# glove-shield.net
KiCad netlist of a schematic drawn in EAGLE
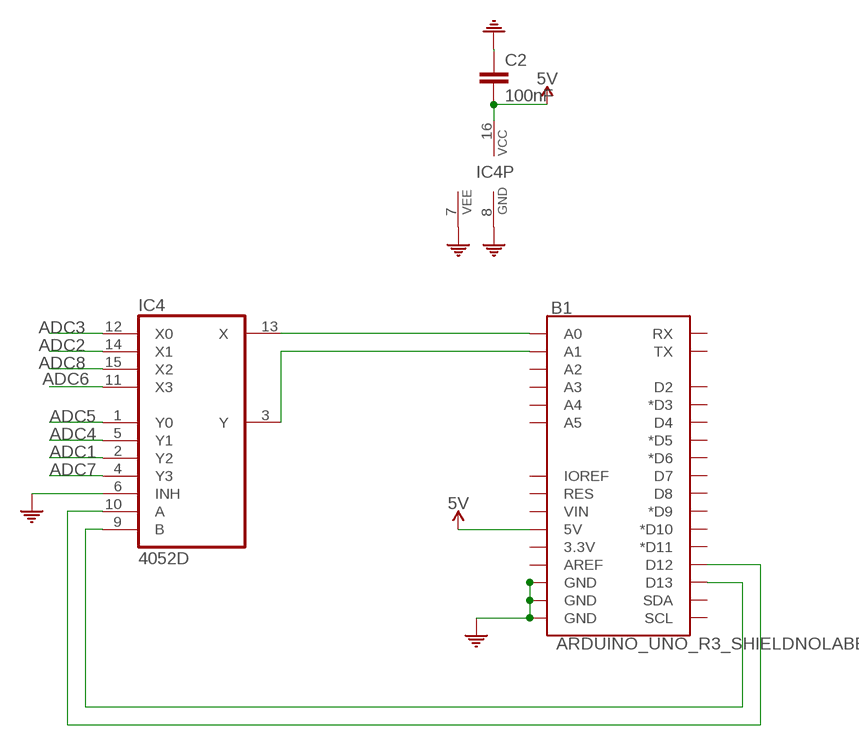
[diagram p0: schematic, sheet 1]
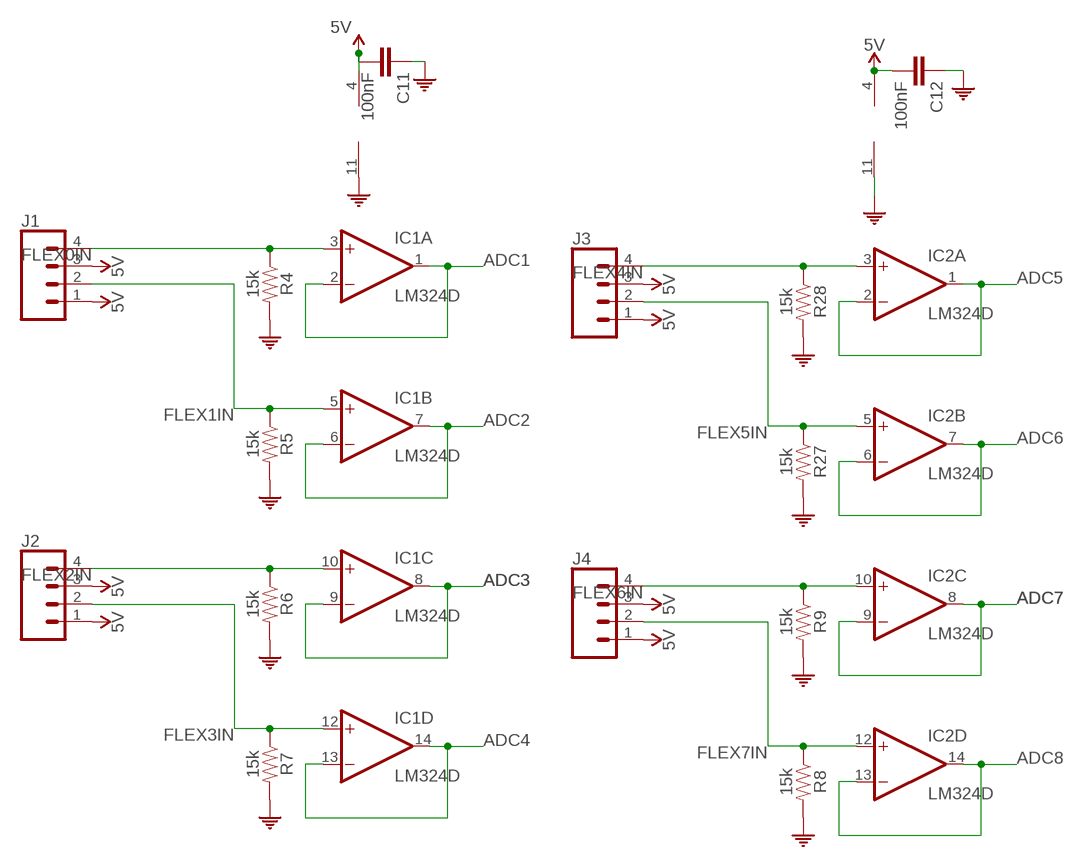
[diagram p1: schematic, sheet 2]

(export (version "E")
  (design (tool "Eeschema 10.0.6"))
  (components
    (comp (ref "C11")
      (value "100nF")
      (footprint "eagle-import:C0603-ROUND")
      (fields (field (name "PART_NUMBER") "cl10b104kbnc"))
      (libsource (lib "eagle-import") (part "0015_100NF_0603"))
    )
    (comp (ref "C12")
      (value "100nF")
      (footprint "eagle-import:C0603-ROUND")
      (fields (field (name "PART_NUMBER") "cl10b104kbnc"))
      (libsource (lib "eagle-import") (part "0015_100NF_0603"))
    )
    (comp (ref "IC1")
      (value "LM324D")
      (footprint "eagle-import:SO14")
      (libsource (lib "eagle-import") (part "LM324D"))
    )
    (comp (ref "IC2")
      (value "LM324D")
      (footprint "eagle-import:SO14")
      (libsource (lib "eagle-import") (part "LM324D"))
    )
    (comp (ref "J1")
      (value "CONN_04JST-PTH")
      (footprint "eagle-import:JST-4-PTH")
      (libsource (lib "eagle-import") (part "CONN_04JST-PTH"))
    )
    (comp (ref "J2")
      (value "CONN_04JST-PTH")
      (footprint "eagle-import:JST-4-PTH")
      (libsource (lib "eagle-import") (part "CONN_04JST-PTH"))
    )
    (comp (ref "J3")
      (value "CONN_04JST-PTH")
      (footprint "eagle-import:JST-4-PTH")
      (libsource (lib "eagle-import") (part "CONN_04JST-PTH"))
    )
    (comp (ref "J4")
      (value "CONN_04JST-PTH")
      (footprint "eagle-import:JST-4-PTH")
      (libsource (lib "eagle-import") (part "CONN_04JST-PTH"))
    )
    (comp (ref "R4")
      (value "15k")
      (footprint "eagle-import:0603")
      (libsource (lib "eagle-import") (part "RESISTOR0603"))
    )
    (comp (ref "R5")
      (value "15k")
      (footprint "eagle-import:0603")
      (libsource (lib "eagle-import") (part "RESISTOR0603"))
    )
    (comp (ref "R6")
      (value "15k")
      (footprint "eagle-import:0603")
      (libsource (lib "eagle-import") (part "RESISTOR0603"))
    )
    (comp (ref "R7")
      (value "15k")
      (footprint "eagle-import:0603")
      (libsource (lib "eagle-import") (part "RESISTOR0603"))
    )
    (comp (ref "R8")
      (value "15k")
      (footprint "eagle-import:0603")
      (libsource (lib "eagle-import") (part "RESISTOR0603"))
    )
    (comp (ref "R9")
      (value "15k")
      (footprint "eagle-import:0603")
      (libsource (lib "eagle-import") (part "RESISTOR0603"))
    )
    (comp (ref "R27")
      (value "15k")
      (footprint "eagle-import:0603")
      (libsource (lib "eagle-import") (part "RESISTOR0603"))
    )
    (comp (ref "R28")
      (value "15k")
      (footprint "eagle-import:0603")
      (libsource (lib "eagle-import") (part "RESISTOR0603"))
    )
    (comp (ref "B1")
      (value "ARDUINO_UNO_R3_SHIELDNOLABELS")
      (footprint "eagle-import:UNO_R3_SHIELD_NOLABELS")
      (libsource (lib "eagle-import") (part "ARDUINO_UNO_R3_SHIELDNOLABELS"))
    )
    (comp (ref "C2")
      (value "100nF")
      (footprint "eagle-import:C0603-ROUND")
      (fields (field (name "PART_NUMBER") "cl10b104kbnc"))
      (libsource (lib "eagle-import") (part "0015_100NF_0603"))
    )
    (comp (ref "IC4")
      (value "4052D")
      (footprint "eagle-import:SO16")
      (libsource (lib "eagle-import") (part "4052D"))
    )
  )
  (nets
    (net (code "1") (name "5V") (class "Default")
      (node (ref "B1") (pin "5V") (pinfunction "5V_5V") (pintype "bidirectional"))
      (node (ref "C11") (pin "2") (pinfunction "2_2") (pintype "passive"))
      (node (ref "C12") (pin "2") (pinfunction "2_2") (pintype "passive"))
      (node (ref "C2") (pin "2") (pinfunction "2_2") (pintype "passive"))
      (node (ref "IC1") (pin "4") (pinfunction "V+_4") (pintype "power_in"))
      (node (ref "IC2") (pin "4") (pinfunction "V+_4") (pintype "power_in"))
      (node (ref "IC4") (pin "16") (pinfunction "VCC_16") (pintype "power_in"))
      (node (ref "J1") (pin "1") (pinfunction "1_1") (pintype "passive"))
      (node (ref "J1") (pin "3") (pinfunction "3_3") (pintype "passive"))
      (node (ref "J2") (pin "1") (pinfunction "1_1") (pintype "passive"))
      (node (ref "J2") (pin "3") (pinfunction "3_3") (pintype "passive"))
      (node (ref "J3") (pin "1") (pinfunction "1_1") (pintype "passive"))
      (node (ref "J3") (pin "3") (pinfunction "3_3") (pintype "passive"))
      (node (ref "J4") (pin "1") (pinfunction "1_1") (pintype "passive"))
      (node (ref "J4") (pin "3") (pinfunction "3_3") (pintype "passive"))
    )
    (net (code "2") (name "ADC1") (class "Default")
      (node (ref "IC1") (pin "1") (pinfunction "OUT_1") (pintype "output"))
      (node (ref "IC1") (pin "2") (pinfunction "-IN_2") (pintype "input"))
      (node (ref "IC4") (pin "2") (pinfunction "Y2_2") (pintype "bidirectional"))
    )
    (net (code "3") (name "ADC2") (class "Default")
      (node (ref "IC1") (pin "6") (pinfunction "-IN_6") (pintype "input"))
      (node (ref "IC1") (pin "7") (pinfunction "OUT_7") (pintype "output"))
      (node (ref "IC4") (pin "14") (pinfunction "X1_14") (pintype "bidirectional"))
    )
    (net (code "4") (name "ADC3") (class "Default")
      (node (ref "IC1") (pin "8") (pinfunction "OUT_8") (pintype "output"))
      (node (ref "IC1") (pin "9") (pinfunction "-IN_9") (pintype "input"))
      (node (ref "IC4") (pin "12") (pinfunction "X0_12") (pintype "bidirectional"))
    )
    (net (code "5") (name "ADC4") (class "Default")
      (node (ref "IC1") (pin "13") (pinfunction "-IN_13") (pintype "input"))
      (node (ref "IC1") (pin "14") (pinfunction "OUT_14") (pintype "output"))
      (node (ref "IC4") (pin "5") (pinfunction "Y1_5") (pintype "bidirectional"))
    )
    (net (code "6") (name "ADC5") (class "Default")
      (node (ref "IC2") (pin "1") (pinfunction "OUT_1") (pintype "output"))
      (node (ref "IC2") (pin "2") (pinfunction "-IN_2") (pintype "input"))
      (node (ref "IC4") (pin "1") (pinfunction "Y0_1") (pintype "bidirectional"))
    )
    (net (code "7") (name "ADC6") (class "Default")
      (node (ref "IC2") (pin "6") (pinfunction "-IN_6") (pintype "input"))
      (node (ref "IC2") (pin "7") (pinfunction "OUT_7") (pintype "output"))
      (node (ref "IC4") (pin "11") (pinfunction "X3_11") (pintype "bidirectional"))
    )
    (net (code "8") (name "ADC7") (class "Default")
      (node (ref "IC2") (pin "8") (pinfunction "OUT_8") (pintype "output"))
      (node (ref "IC2") (pin "9") (pinfunction "-IN_9") (pintype "input"))
      (node (ref "IC4") (pin "4") (pinfunction "Y3_4") (pintype "bidirectional"))
    )
    (net (code "9") (name "ADC8") (class "Default")
      (node (ref "IC2") (pin "13") (pinfunction "-IN_13") (pintype "input"))
      (node (ref "IC2") (pin "14") (pinfunction "OUT_14") (pintype "output"))
      (node (ref "IC4") (pin "15") (pinfunction "X2_15") (pintype "bidirectional"))
    )
    (net (code "10") (name "COM") (class "Default")
      (node (ref "B1") (pin "GND@0") (pinfunction "GND_GND@0") (pintype "bidirectional"))
      (node (ref "B1") (pin "GND@1") (pinfunction "GND_GND@1") (pintype "bidirectional"))
      (node (ref "B1") (pin "GND@2") (pinfunction "GND_GND@2") (pintype "bidirectional"))
      (node (ref "C11") (pin "1") (pinfunction "1_1") (pintype "passive"))
      (node (ref "C12") (pin "1") (pinfunction "1_1") (pintype "passive"))
      (node (ref "C2") (pin "1") (pinfunction "1_1") (pintype "passive"))
      (node (ref "IC1") (pin "11") (pinfunction "V-_11") (pintype "power_in"))
      (node (ref "IC2") (pin "11") (pinfunction "V-_11") (pintype "power_in"))
      (node (ref "IC4") (pin "6") (pinfunction "INH_6") (pintype "input"))
      (node (ref "IC4") (pin "7") (pinfunction "VEE_7") (pintype "power_in"))
      (node (ref "IC4") (pin "8") (pinfunction "GND_8") (pintype "power_in"))
      (node (ref "R27") (pin "2") (pinfunction "2_2") (pintype "passive"))
      (node (ref "R28") (pin "2") (pinfunction "2_2") (pintype "passive"))
      (node (ref "R4") (pin "2") (pinfunction "2_2") (pintype "passive"))
      (node (ref "R5") (pin "2") (pinfunction "2_2") (pintype "passive"))
      (node (ref "R6") (pin "2") (pinfunction "2_2") (pintype "passive"))
      (node (ref "R7") (pin "2") (pinfunction "2_2") (pintype "passive"))
      (node (ref "R8") (pin "2") (pinfunction "2_2") (pintype "passive"))
      (node (ref "R9") (pin "2") (pinfunction "2_2") (pintype "passive"))
    )
    (net (code "11") (name "FLEX0IN") (class "Default")
      (node (ref "IC1") (pin "3") (pinfunction "+IN_3") (pintype "input"))
      (node (ref "J1") (pin "4") (pinfunction "4_4") (pintype "passive"))
      (node (ref "R4") (pin "1") (pinfunction "1_1") (pintype "passive"))
    )
    (net (code "12") (name "FLEX1IN") (class "Default")
      (node (ref "IC1") (pin "5") (pinfunction "+IN_5") (pintype "input"))
      (node (ref "J1") (pin "2") (pinfunction "2_2") (pintype "passive"))
      (node (ref "R5") (pin "1") (pinfunction "1_1") (pintype "passive"))
    )
    (net (code "13") (name "FLEX2IN") (class "Default")
      (node (ref "IC1") (pin "10") (pinfunction "+IN_10") (pintype "input"))
      (node (ref "J2") (pin "4") (pinfunction "4_4") (pintype "passive"))
      (node (ref "R6") (pin "1") (pinfunction "1_1") (pintype "passive"))
    )
    (net (code "14") (name "FLEX3IN") (class "Default")
      (node (ref "IC1") (pin "12") (pinfunction "+IN_12") (pintype "input"))
      (node (ref "J2") (pin "2") (pinfunction "2_2") (pintype "passive"))
      (node (ref "R7") (pin "1") (pinfunction "1_1") (pintype "passive"))
    )
    (net (code "15") (name "FLEX4IN") (class "Default")
      (node (ref "IC2") (pin "3") (pinfunction "+IN_3") (pintype "input"))
      (node (ref "J3") (pin "4") (pinfunction "4_4") (pintype "passive"))
      (node (ref "R28") (pin "1") (pinfunction "1_1") (pintype "passive"))
    )
    (net (code "16") (name "FLEX5IN") (class "Default")
      (node (ref "IC2") (pin "5") (pinfunction "+IN_5") (pintype "input"))
      (node (ref "J3") (pin "2") (pinfunction "2_2") (pintype "passive"))
      (node (ref "R27") (pin "1") (pinfunction "1_1") (pintype "passive"))
    )
    (net (code "17") (name "FLEX6IN") (class "Default")
      (node (ref "IC2") (pin "10") (pinfunction "+IN_10") (pintype "input"))
      (node (ref "J4") (pin "4") (pinfunction "4_4") (pintype "passive"))
      (node (ref "R9") (pin "1") (pinfunction "1_1") (pintype "passive"))
    )
    (net (code "18") (name "FLEX7IN") (class "Default")
      (node (ref "IC2") (pin "12") (pinfunction "+IN_12") (pintype "input"))
      (node (ref "J4") (pin "2") (pinfunction "2_2") (pintype "passive"))
      (node (ref "R8") (pin "1") (pinfunction "1_1") (pintype "passive"))
    )
    (net (code "19") (name "Net-(IC4A-A)") (class "Default")
      (node (ref "B1") (pin "D12") (pinfunction "D12_D12") (pintype "bidirectional"))
      (node (ref "IC4") (pin "10") (pinfunction "A_10") (pintype "input"))
    )
    (net (code "20") (name "Net-(IC4A-B)") (class "Default")
      (node (ref "B1") (pin "D13") (pinfunction "D13_D13") (pintype "bidirectional"))
      (node (ref "IC4") (pin "9") (pinfunction "B_9") (pintype "input"))
    )
    (net (code "21") (name "Net-(IC4A-X)") (class "Default")
      (node (ref "B1") (pin "A0") (pinfunction "A0_A0") (pintype "bidirectional"))
      (node (ref "IC4") (pin "13") (pinfunction "X_13") (pintype "bidirectional"))
    )
    (net (code "22") (name "Net-(IC4A-Y)") (class "Default")
      (node (ref "B1") (pin "A1") (pinfunction "A1_A1") (pintype "bidirectional"))
      (node (ref "IC4") (pin "3") (pinfunction "Y_3") (pintype "bidirectional"))
    )
    (net (code "23") (name "unconnected-(B1-*D3-PadD3)") (class "Default")
      (node (ref "B1") (pin "D3") (pinfunction "*D3_D3") (pintype "bidirectional"))
    )
    (net (code "24") (name "unconnected-(B1-*D5-PadD5)") (class "Default")
      (node (ref "B1") (pin "D5") (pinfunction "*D5_D5") (pintype "bidirectional"))
    )
    (net (code "25") (name "unconnected-(B1-*D6-PadD6)") (class "Default")
      (node (ref "B1") (pin "D6") (pinfunction "*D6_D6") (pintype "bidirectional"))
    )
    (net (code "26") (name "unconnected-(B1-*D9-PadD9)") (class "Default")
      (node (ref "B1") (pin "D9") (pinfunction "*D9_D9") (pintype "bidirectional"))
    )
    (net (code "27") (name "unconnected-(B1-*D10-PadD10)") (class "Default")
      (node (ref "B1") (pin "D10") (pinfunction "*D10_D10") (pintype "bidirectional"))
    )
    (net (code "28") (name "unconnected-(B1-*D11-PadD11)") (class "Default")
      (node (ref "B1") (pin "D11") (pinfunction "*D11_D11") (pintype "bidirectional"))
    )
    (net (code "29") (name "unconnected-(B1-Pad3.3V)") (class "Default")
      (node (ref "B1") (pin "3.3V") (pinfunction "3.3V_3.3V") (pintype "bidirectional"))
    )
    (net (code "30") (name "unconnected-(B1-PadA2)") (class "Default")
      (node (ref "B1") (pin "A2") (pinfunction "A2_A2") (pintype "bidirectional"))
    )
    (net (code "31") (name "unconnected-(B1-PadA3)") (class "Default")
      (node (ref "B1") (pin "A3") (pinfunction "A3_A3") (pintype "bidirectional"))
    )
    (net (code "32") (name "unconnected-(B1-PadA4)") (class "Default")
      (node (ref "B1") (pin "A4") (pinfunction "A4_A4") (pintype "bidirectional"))
    )
    (net (code "33") (name "unconnected-(B1-PadA5)") (class "Default")
      (node (ref "B1") (pin "A5") (pinfunction "A5_A5") (pintype "bidirectional"))
    )
    (net (code "34") (name "unconnected-(B1-PadAREF)") (class "Default")
      (node (ref "B1") (pin "AREF") (pinfunction "AREF_AREF") (pintype "bidirectional"))
    )
    (net (code "35") (name "unconnected-(B1-PadD2)") (class "Default")
      (node (ref "B1") (pin "D2") (pinfunction "D2_D2") (pintype "bidirectional"))
    )
    (net (code "36") (name "unconnected-(B1-PadD4)") (class "Default")
      (node (ref "B1") (pin "D4") (pinfunction "D4_D4") (pintype "bidirectional"))
    )
    (net (code "37") (name "unconnected-(B1-PadD7)") (class "Default")
      (node (ref "B1") (pin "D7") (pinfunction "D7_D7") (pintype "bidirectional"))
    )
    (net (code "38") (name "unconnected-(B1-PadD8)") (class "Default")
      (node (ref "B1") (pin "D8") (pinfunction "D8_D8") (pintype "bidirectional"))
    )
    (net (code "39") (name "unconnected-(B1-PadIOREF)") (class "Default")
      (node (ref "B1") (pin "IOREF") (pinfunction "IOREF_IOREF") (pintype "bidirectional"))
    )
    (net (code "40") (name "unconnected-(B1-PadRES)") (class "Default")
      (node (ref "B1") (pin "RES") (pinfunction "RES_RES") (pintype "bidirectional"))
    )
    (net (code "41") (name "unconnected-(B1-PadRX)") (class "Default")
      (node (ref "B1") (pin "RX") (pinfunction "RX_RX") (pintype "bidirectional"))
    )
    (net (code "42") (name "unconnected-(B1-PadSCL)") (class "Default")
      (node (ref "B1") (pin "SCL") (pinfunction "SCL_SCL") (pintype "bidirectional"))
    )
    (net (code "43") (name "unconnected-(B1-PadSDA)") (class "Default")
      (node (ref "B1") (pin "SDA") (pinfunction "SDA_SDA") (pintype "bidirectional"))
    )
    (net (code "44") (name "unconnected-(B1-PadTX)") (class "Default")
      (node (ref "B1") (pin "TX") (pinfunction "TX_TX") (pintype "bidirectional"))
    )
    (net (code "45") (name "unconnected-(B1-PadVIN)") (class "Default")
      (node (ref "B1") (pin "VIN") (pinfunction "VIN_VIN") (pintype "bidirectional"))
    )
  )
)
